# MCU.net
KiCad netlist of a schematic drawn in Altium Designer
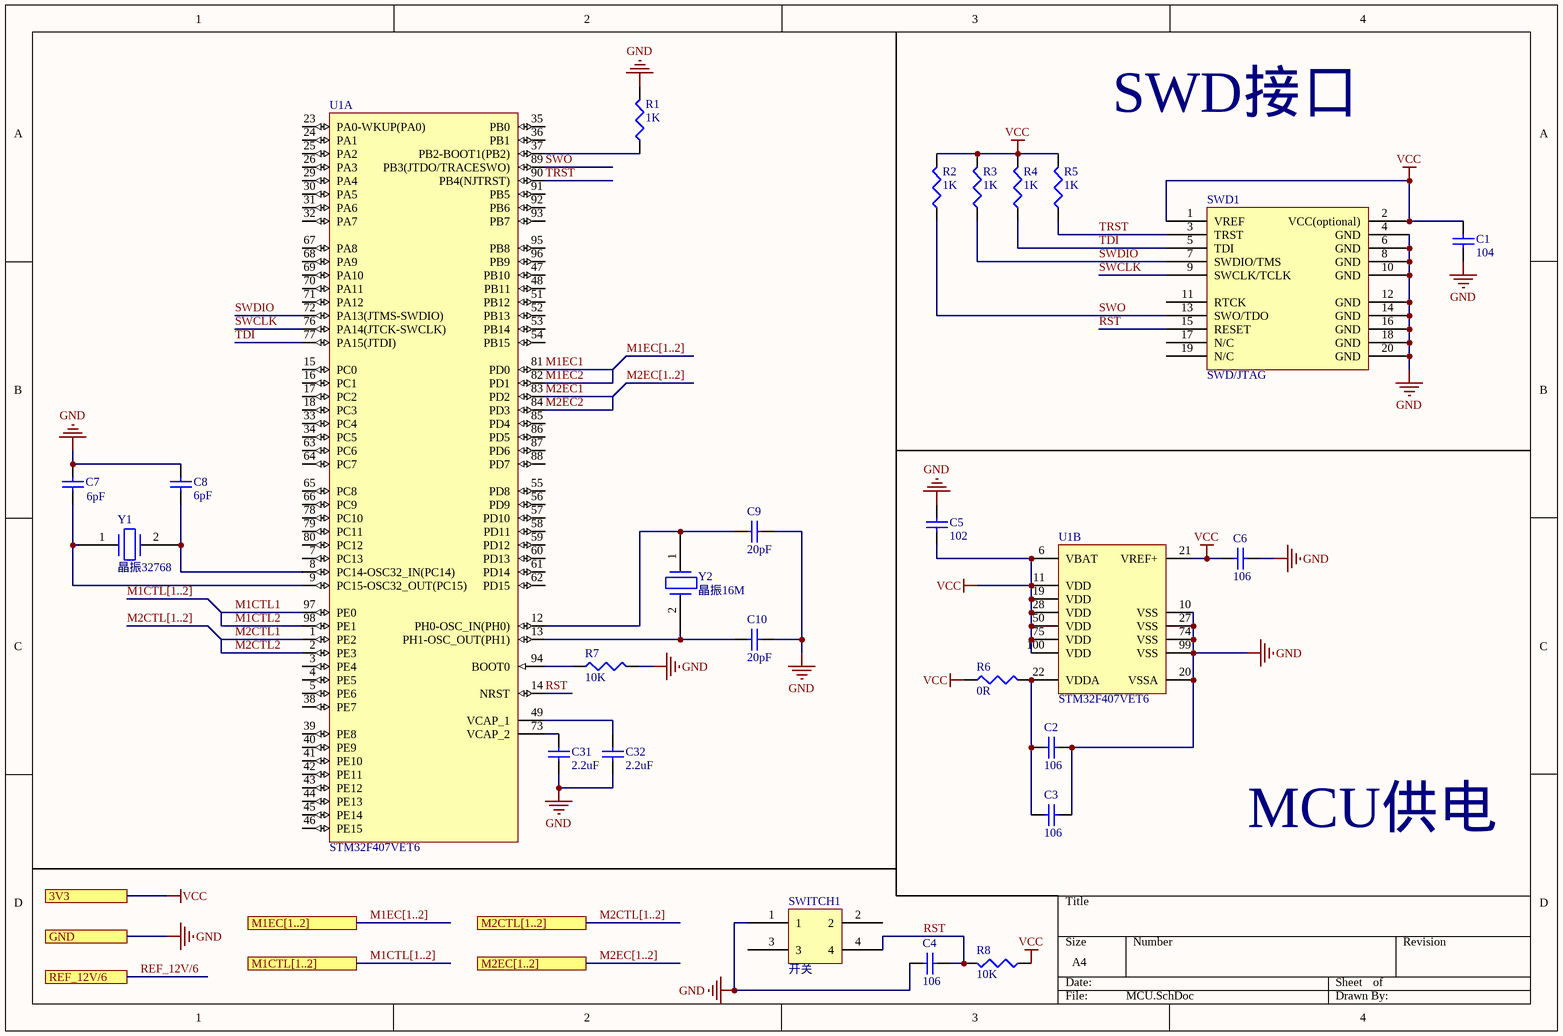
[diagram p0: MCU.SchDoc]

(export (version "E")
  (design (tool "Eeschema 10.0.6"))
  (components
    (comp (ref "C1")
      (value "104")
      (footprint "MY0805")
      (description "Capacitor")
      (fields (field (name "PUBLISHER") "Altium Limited"))
      (libsource (lib "Miscellaneous Devices") (part "Cap"))
    )
    (comp (ref "C2")
      (value "106")
      (footprint "MY0805")
      (description "Capacitor")
      (fields (field (name "PUBLISHER") "Altium Limited"))
      (libsource (lib "Miscellaneous Devices") (part "Cap"))
    )
    (comp (ref "C3")
      (value "106")
      (footprint "MY0805")
      (description "Capacitor")
      (fields (field (name "PUBLISHER") "Altium Limited"))
      (libsource (lib "Miscellaneous Devices") (part "Cap"))
    )
    (comp (ref "C4")
      (value "106")
      (footprint "MY0805")
      (description "Capacitor")
      (fields (field (name "PUBLISHER") "Altium Limited"))
      (libsource (lib "Miscellaneous Devices") (part "Cap"))
    )
    (comp (ref "C5")
      (value "102")
      (footprint "MY0805")
      (description "Capacitor")
      (fields (field (name "PUBLISHER") "Altium Limited"))
      (libsource (lib "Miscellaneous Devices") (part "Cap"))
    )
    (comp (ref "C6")
      (value "106")
      (footprint "MY0805")
      (description "Capacitor")
      (fields (field (name "PUBLISHER") "Altium Limited"))
      (libsource (lib "Miscellaneous Devices") (part "Cap"))
    )
    (comp (ref "C7")
      (value "6pF")
      (footprint "MY0805")
      (description "Capacitor")
      (fields (field (name "PUBLISHER") "Altium Limited"))
      (libsource (lib "Miscellaneous Devices") (part "Cap"))
    )
    (comp (ref "C8")
      (value "6pF")
      (footprint "MY0805")
      (description "Capacitor")
      (fields (field (name "PUBLISHER") "Altium Limited"))
      (libsource (lib "Miscellaneous Devices") (part "Cap"))
    )
    (comp (ref "C9")
      (value "20pF")
      (footprint "MY0805")
      (description "Capacitor")
      (fields (field (name "PUBLISHER") "Altium Limited"))
      (libsource (lib "Miscellaneous Devices") (part "Cap"))
    )
    (comp (ref "C10")
      (value "20pF")
      (footprint "MY0805")
      (description "Capacitor")
      (fields (field (name "PUBLISHER") "Altium Limited"))
      (libsource (lib "Miscellaneous Devices") (part "Cap"))
    )
    (comp (ref "C31")
      (value "2.2uF")
      (footprint "MY0805")
      (description "Capacitor")
      (fields (field (name "PUBLISHER") "Altium Limited"))
      (libsource (lib "Miscellaneous Devices") (part "Cap"))
    )
    (comp (ref "C32")
      (value "2.2uF")
      (footprint "MY0805")
      (description "Capacitor")
      (fields (field (name "PUBLISHER") "Altium Limited"))
      (libsource (lib "Miscellaneous Devices") (part "Cap"))
    )
    (comp (ref "R1")
      (value "1K")
      (footprint "MY0805")
      (description "Resistor")
      (fields (field (name "PUBLISHER") "Altium Limited"))
      (libsource (lib "Miscellaneous Devices") (part "Res3"))
    )
    (comp (ref "R2")
      (value "1K")
      (footprint "MY0805")
      (description "Resistor")
      (fields (field (name "PUBLISHER") "Altium Limited"))
      (libsource (lib "Miscellaneous Devices") (part "Res3"))
    )
    (comp (ref "R3")
      (value "1K")
      (footprint "MY0805")
      (description "Resistor")
      (fields (field (name "PUBLISHER") "Altium Limited"))
      (libsource (lib "Miscellaneous Devices") (part "Res3"))
    )
    (comp (ref "R4")
      (value "1K")
      (footprint "MY0805")
      (description "Resistor")
      (fields (field (name "PUBLISHER") "Altium Limited"))
      (libsource (lib "Miscellaneous Devices") (part "Res3"))
    )
    (comp (ref "R5")
      (value "1K")
      (footprint "MY0805")
      (description "Resistor")
      (fields (field (name "PUBLISHER") "Altium Limited"))
      (libsource (lib "Miscellaneous Devices") (part "Res3"))
    )
    (comp (ref "R6")
      (value "0R")
      (footprint "MY0805")
      (description "Resistor")
      (fields (field (name "PUBLISHER") "Altium Limited"))
      (libsource (lib "Miscellaneous Devices") (part "Res3"))
    )
    (comp (ref "R7")
      (value "10K")
      (footprint "MY0805")
      (description "Resistor")
      (fields (field (name "PUBLISHER") "Altium Limited"))
      (libsource (lib "Miscellaneous Devices") (part "Res3"))
    )
    (comp (ref "R8")
      (value "10K")
      (footprint "MY0805")
      (description "Resistor")
      (fields (field (name "PUBLISHER") "Altium Limited"))
      (libsource (lib "Miscellaneous Devices") (part "Res3"))
    )
    (comp (ref "SWD1") (value "SWD/JTAG") (footprint "SWD") (libsource (lib "Schlib1") (part "SWD/JTAG")))
    (comp (ref "SWITCH1") (value "开关") (footprint "开关") (libsource (lib "Schlib1") (part "开关")))
    (comp (ref "U1")
      (value "STM32F407VET6")
      (footprint "STM-LQFP100_N")
      (fields (field (name "MANUFACTURER") "STMicroelectronics"))
      (libsource (lib "STMicroelectronics STM32 F4") (part "STM32F407VET6"))
    )
    (comp (ref "Y1") (value "晶振32768") (footprint "晶振32768K_AT38") (libsource (lib "Schlib1") (part "晶振")))
    (comp (ref "Y2") (value "晶振16M") (footprint "晶振16M") (libsource (lib "Schlib1") (part "晶振")))
  )
  (nets
    (net (code "1") (name "/M1CTL1") (class "Default")
      (node (ref "U1") (pin "97") (pinfunction "PE0_97") (pintype "bidirectional"))
    )
    (net (code "2") (name "/M1CTL2") (class "Default")
      (node (ref "U1") (pin "98") (pinfunction "PE1_98") (pintype "bidirectional"))
    )
    (net (code "4") (name "/M1EC1") (class "Default")
      (node (ref "U1") (pin "81") (pinfunction "PD0_81") (pintype "bidirectional"))
    )
    (net (code "5") (name "/M1EC2") (class "Default")
      (node (ref "U1") (pin "82") (pinfunction "PD1_82") (pintype "bidirectional"))
    )
    (net (code "7") (name "/M2CTL1") (class "Default")
      (node (ref "U1") (pin "1") (pinfunction "PE2_1") (pintype "bidirectional"))
    )
    (net (code "8") (name "/M2CTL2") (class "Default")
      (node (ref "U1") (pin "2") (pinfunction "PE3_2") (pintype "bidirectional"))
    )
    (net (code "10") (name "/M2EC1") (class "Default")
      (node (ref "U1") (pin "83") (pinfunction "PD2_83") (pintype "bidirectional"))
    )
    (net (code "11") (name "/M2EC2") (class "Default")
      (node (ref "U1") (pin "84") (pinfunction "PD3_84") (pintype "bidirectional"))
    )
    (net (code "14") (name "/RST") (class "Default")
      (node (ref "C4") (pin "2") (pinfunction "2_2") (pintype "passive"))
      (node (ref "R8") (pin "2") (pinfunction "2_2") (pintype "passive"))
      (node (ref "SWD1") (pin "15") (pinfunction "RESET_15") (pintype "passive"))
      (node (ref "SWITCH1") (pin "4") (pinfunction "4_4") (pintype "passive"))
      (node (ref "U1") (pin "14") (pinfunction "NRST_14") (pintype "bidirectional"))
    )
    (net (code "15") (name "/SWCLK") (class "Default")
      (node (ref "SWD1") (pin "9") (pinfunction "SWCLK/TCLK_9") (pintype "passive"))
      (node (ref "U1") (pin "76") (pinfunction "PA14(JTCK-SWCLK)_76") (pintype "bidirectional"))
    )
    (net (code "16") (name "/SWDIO") (class "Default")
      (node (ref "R3") (pin "1") (pinfunction "1_1") (pintype "passive"))
      (node (ref "SWD1") (pin "7") (pinfunction "SWDIO/TMS_7") (pintype "passive"))
      (node (ref "U1") (pin "72") (pinfunction "PA13(JTMS-SWDIO)_72") (pintype "bidirectional"))
    )
    (net (code "17") (name "/SWO") (class "Default")
      (node (ref "R2") (pin "1") (pinfunction "1_1") (pintype "passive"))
      (node (ref "SWD1") (pin "13") (pinfunction "SWO/TDO_13") (pintype "passive"))
      (node (ref "U1") (pin "89") (pinfunction "PB3(JTDO/TRACESWO)_89") (pintype "bidirectional"))
    )
    (net (code "18") (name "/TDI") (class "Default")
      (node (ref "R4") (pin "1") (pinfunction "1_1") (pintype "passive"))
      (node (ref "SWD1") (pin "5") (pinfunction "TDI_5") (pintype "passive"))
      (node (ref "U1") (pin "77") (pinfunction "PA15(JTDI)_77") (pintype "bidirectional"))
    )
    (net (code "19") (name "/TRST") (class "Default")
      (node (ref "R5") (pin "1") (pinfunction "1_1") (pintype "passive"))
      (node (ref "SWD1") (pin "3") (pinfunction "TRST_3") (pintype "passive"))
      (node (ref "U1") (pin "90") (pinfunction "PB4(NJTRST)_90") (pintype "bidirectional"))
    )
    (net (code "20") (name "GND") (class "Default")
      (node (ref "C1") (pin "1") (pinfunction "1_1") (pintype "passive"))
      (node (ref "C10") (pin "2") (pinfunction "2_2") (pintype "passive"))
      (node (ref "C2") (pin "2") (pinfunction "2_2") (pintype "passive"))
      (node (ref "C3") (pin "2") (pinfunction "2_2") (pintype "passive"))
      (node (ref "C31") (pin "1") (pinfunction "1_1") (pintype "passive"))
      (node (ref "C32") (pin "1") (pinfunction "1_1") (pintype "passive"))
      (node (ref "C4") (pin "1") (pinfunction "1_1") (pintype "passive"))
      (node (ref "C5") (pin "1") (pinfunction "1_1") (pintype "passive"))
      (node (ref "C6") (pin "2") (pinfunction "2_2") (pintype "passive"))
      (node (ref "C7") (pin "2") (pinfunction "2_2") (pintype "passive"))
      (node (ref "C8") (pin "2") (pinfunction "2_2") (pintype "passive"))
      (node (ref "C9") (pin "2") (pinfunction "2_2") (pintype "passive"))
      (node (ref "R1") (pin "2") (pinfunction "2_2") (pintype "passive"))
      (node (ref "R7") (pin "2") (pinfunction "2_2") (pintype "passive"))
      (node (ref "SWD1") (pin "10") (pinfunction "GND_10") (pintype "passive"))
      (node (ref "SWD1") (pin "12") (pinfunction "GND_12") (pintype "passive"))
      (node (ref "SWD1") (pin "14") (pinfunction "GND_14") (pintype "passive"))
      (node (ref "SWD1") (pin "16") (pinfunction "GND_16") (pintype "passive"))
      (node (ref "SWD1") (pin "18") (pinfunction "GND_18") (pintype "passive"))
      (node (ref "SWD1") (pin "20") (pinfunction "GND_20") (pintype "passive"))
      (node (ref "SWD1") (pin "4") (pinfunction "GND_4") (pintype "passive"))
      (node (ref "SWD1") (pin "6") (pinfunction "GND_6") (pintype "passive"))
      (node (ref "SWD1") (pin "8") (pinfunction "GND_8") (pintype "passive"))
      (node (ref "SWITCH1") (pin "1") (pinfunction "1_1") (pintype "passive"))
      (node (ref "U1") (pin "10") (pinfunction "VSS_10") (pintype "power_in"))
      (node (ref "U1") (pin "20") (pinfunction "VSSA_20") (pintype "power_in"))
      (node (ref "U1") (pin "27") (pinfunction "VSS_27") (pintype "power_in"))
      (node (ref "U1") (pin "74") (pinfunction "VSS_74") (pintype "power_in"))
      (node (ref "U1") (pin "99") (pinfunction "VSS_99") (pintype "power_in"))
    )
    (net (code "21") (name "Net-(U1A-BOOT0)") (class "Default")
      (node (ref "R7") (pin "1") (pinfunction "1_1") (pintype "passive"))
      (node (ref "U1") (pin "94") (pinfunction "BOOT0_94") (pintype "input"))
    )
    (net (code "22") (name "Net-(U1A-PB2-BOOT1(PB2))") (class "Default")
      (node (ref "R1") (pin "1") (pinfunction "1_1") (pintype "passive"))
      (node (ref "U1") (pin "37") (pinfunction "PB2-BOOT1(PB2)_37") (pintype "bidirectional"))
    )
    (net (code "23") (name "Net-(U1A-PC14-OSC32_IN(PC14))") (class "Default")
      (node (ref "C8") (pin "1") (pinfunction "1_1") (pintype "passive"))
      (node (ref "U1") (pin "8") (pinfunction "PC14-OSC32_IN(PC14)_8") (pintype "bidirectional"))
      (node (ref "Y1") (pin "2") (pinfunction "2_2") (pintype "passive"))
    )
    (net (code "24") (name "Net-(U1A-PC15-OSC32_OUT(PC15))") (class "Default")
      (node (ref "C7") (pin "1") (pinfunction "1_1") (pintype "passive"))
      (node (ref "U1") (pin "9") (pinfunction "PC15-OSC32_OUT(PC15)_9") (pintype "bidirectional"))
      (node (ref "Y1") (pin "1") (pinfunction "1_1") (pintype "passive"))
    )
    (net (code "25") (name "Net-(U1A-PH0-OSC_IN(PH0))") (class "Default")
      (node (ref "C9") (pin "1") (pinfunction "1_1") (pintype "passive"))
      (node (ref "U1") (pin "12") (pinfunction "PH0-OSC_IN(PH0)_12") (pintype "bidirectional"))
      (node (ref "Y2") (pin "1") (pinfunction "1_1") (pintype "passive"))
    )
    (net (code "26") (name "Net-(U1A-PH1-OSC_OUT(PH1))") (class "Default")
      (node (ref "C10") (pin "1") (pinfunction "1_1") (pintype "passive"))
      (node (ref "U1") (pin "13") (pinfunction "PH1-OSC_OUT(PH1)_13") (pintype "bidirectional"))
      (node (ref "Y2") (pin "2") (pinfunction "2_2") (pintype "passive"))
    )
    (net (code "27") (name "Net-(U1A-VCAP_1)") (class "Default")
      (node (ref "C32") (pin "2") (pinfunction "2_2") (pintype "passive"))
      (node (ref "U1") (pin "49") (pinfunction "VCAP_1_49") (pintype "power_in"))
    )
    (net (code "28") (name "Net-(U1A-VCAP_2)") (class "Default")
      (node (ref "C31") (pin "2") (pinfunction "2_2") (pintype "passive"))
      (node (ref "U1") (pin "73") (pinfunction "VCAP_2_73") (pintype "power_in"))
    )
    (net (code "29") (name "Net-(U1B-VDDA)") (class "Default")
      (node (ref "C2") (pin "1") (pinfunction "1_1") (pintype "passive"))
      (node (ref "C3") (pin "1") (pinfunction "1_1") (pintype "passive"))
      (node (ref "R6") (pin "2") (pinfunction "2_2") (pintype "passive"))
      (node (ref "U1") (pin "22") (pinfunction "VDDA_22") (pintype "power_in"))
    )
    (net (code "30") (name "VCC") (class "Default")
      (node (ref "C1") (pin "2") (pinfunction "2_2") (pintype "passive"))
      (node (ref "C5") (pin "2") (pinfunction "2_2") (pintype "passive"))
      (node (ref "C6") (pin "1") (pinfunction "1_1") (pintype "passive"))
      (node (ref "R2") (pin "2") (pinfunction "2_2") (pintype "passive"))
      (node (ref "R3") (pin "2") (pinfunction "2_2") (pintype "passive"))
      (node (ref "R4") (pin "2") (pinfunction "2_2") (pintype "passive"))
      (node (ref "R5") (pin "2") (pinfunction "2_2") (pintype "passive"))
      (node (ref "R6") (pin "1") (pinfunction "1_1") (pintype "passive"))
      (node (ref "R8") (pin "1") (pinfunction "1_1") (pintype "passive"))
      (node (ref "SWD1") (pin "1") (pinfunction "VREF_1") (pintype "passive"))
      (node (ref "SWD1") (pin "2") (pinfunction "VCC(optional)_2") (pintype "passive"))
      (node (ref "U1") (pin "100") (pinfunction "VDD_100") (pintype "power_in"))
      (node (ref "U1") (pin "11") (pinfunction "VDD_11") (pintype "power_in"))
      (node (ref "U1") (pin "19") (pinfunction "VDD_19") (pintype "power_in"))
      (node (ref "U1") (pin "21") (pinfunction "VREF+_21") (pintype "power_in"))
      (node (ref "U1") (pin "28") (pinfunction "VDD_28") (pintype "power_in"))
      (node (ref "U1") (pin "50") (pinfunction "VDD_50") (pintype "power_in"))
      (node (ref "U1") (pin "6") (pinfunction "VBAT_6") (pintype "power_in"))
      (node (ref "U1") (pin "75") (pinfunction "VDD_75") (pintype "power_in"))
    )
    (net (code "31") (name "unconnected-(SWD1-N{slash}C-Pad17)") (class "Default")
      (node (ref "SWD1") (pin "17") (pinfunction "N/C_17") (pintype "passive"))
    )
    (net (code "32") (name "unconnected-(SWD1-N{slash}C-Pad19)") (class "Default")
      (node (ref "SWD1") (pin "19") (pinfunction "N/C_19") (pintype "passive"))
    )
    (net (code "33") (name "unconnected-(SWD1-RTCK-Pad11)") (class "Default")
      (node (ref "SWD1") (pin "11") (pinfunction "RTCK_11") (pintype "passive"))
    )
    (net (code "34") (name "unconnected-(SWITCH1-Pad2)") (class "Default")
      (node (ref "SWITCH1") (pin "2") (pinfunction "2_2") (pintype "passive"))
    )
    (net (code "35") (name "unconnected-(SWITCH1-Pad3)") (class "Default")
      (node (ref "SWITCH1") (pin "3") (pinfunction "3_3") (pintype "passive"))
    )
    (net (code "36") (name "unconnected-(U1A-PA0-WKUP(PA0)-Pad23)") (class "Default")
      (node (ref "U1") (pin "23") (pinfunction "PA0-WKUP(PA0)_23") (pintype "bidirectional"))
    )
    (net (code "37") (name "unconnected-(U1A-PA1-Pad24)") (class "Default")
      (node (ref "U1") (pin "24") (pinfunction "PA1_24") (pintype "bidirectional"))
    )
    (net (code "38") (name "unconnected-(U1A-PA2-Pad25)") (class "Default")
      (node (ref "U1") (pin "25") (pinfunction "PA2_25") (pintype "bidirectional"))
    )
    (net (code "39") (name "unconnected-(U1A-PA3-Pad26)") (class "Default")
      (node (ref "U1") (pin "26") (pinfunction "PA3_26") (pintype "bidirectional"))
    )
    (net (code "40") (name "unconnected-(U1A-PA4-Pad29)") (class "Default")
      (node (ref "U1") (pin "29") (pinfunction "PA4_29") (pintype "bidirectional"))
    )
    (net (code "41") (name "unconnected-(U1A-PA5-Pad30)") (class "Default")
      (node (ref "U1") (pin "30") (pinfunction "PA5_30") (pintype "bidirectional"))
    )
    (net (code "42") (name "unconnected-(U1A-PA6-Pad31)") (class "Default")
      (node (ref "U1") (pin "31") (pinfunction "PA6_31") (pintype "bidirectional"))
    )
    (net (code "43") (name "unconnected-(U1A-PA7-Pad32)") (class "Default")
      (node (ref "U1") (pin "32") (pinfunction "PA7_32") (pintype "bidirectional"))
    )
    (net (code "44") (name "unconnected-(U1A-PA8-Pad67)") (class "Default")
      (node (ref "U1") (pin "67") (pinfunction "PA8_67") (pintype "bidirectional"))
    )
    (net (code "45") (name "unconnected-(U1A-PA9-Pad68)") (class "Default")
      (node (ref "U1") (pin "68") (pinfunction "PA9_68") (pintype "bidirectional"))
    )
    (net (code "46") (name "unconnected-(U1A-PA10-Pad69)") (class "Default")
      (node (ref "U1") (pin "69") (pinfunction "PA10_69") (pintype "bidirectional"))
    )
    (net (code "47") (name "unconnected-(U1A-PA11-Pad70)") (class "Default")
      (node (ref "U1") (pin "70") (pinfunction "PA11_70") (pintype "bidirectional"))
    )
    (net (code "48") (name "unconnected-(U1A-PA12-Pad71)") (class "Default")
      (node (ref "U1") (pin "71") (pinfunction "PA12_71") (pintype "bidirectional"))
    )
    (net (code "49") (name "unconnected-(U1A-PB0-Pad35)") (class "Default")
      (node (ref "U1") (pin "35") (pinfunction "PB0_35") (pintype "bidirectional"))
    )
    (net (code "50") (name "unconnected-(U1A-PB1-Pad36)") (class "Default")
      (node (ref "U1") (pin "36") (pinfunction "PB1_36") (pintype "bidirectional"))
    )
    (net (code "51") (name "unconnected-(U1A-PB5-Pad91)") (class "Default")
      (node (ref "U1") (pin "91") (pinfunction "PB5_91") (pintype "bidirectional"))
    )
    (net (code "52") (name "unconnected-(U1A-PB6-Pad92)") (class "Default")
      (node (ref "U1") (pin "92") (pinfunction "PB6_92") (pintype "bidirectional"))
    )
    (net (code "53") (name "unconnected-(U1A-PB7-Pad93)") (class "Default")
      (node (ref "U1") (pin "93") (pinfunction "PB7_93") (pintype "bidirectional"))
    )
    (net (code "54") (name "unconnected-(U1A-PB8-Pad95)") (class "Default")
      (node (ref "U1") (pin "95") (pinfunction "PB8_95") (pintype "bidirectional"))
    )
    (net (code "55") (name "unconnected-(U1A-PB9-Pad96)") (class "Default")
      (node (ref "U1") (pin "96") (pinfunction "PB9_96") (pintype "bidirectional"))
    )
    (net (code "56") (name "unconnected-(U1A-PB10-Pad47)") (class "Default")
      (node (ref "U1") (pin "47") (pinfunction "PB10_47") (pintype "bidirectional"))
    )
    (net (code "57") (name "unconnected-(U1A-PB11-Pad48)") (class "Default")
      (node (ref "U1") (pin "48") (pinfunction "PB11_48") (pintype "bidirectional"))
    )
    (net (code "58") (name "unconnected-(U1A-PB12-Pad51)") (class "Default")
      (node (ref "U1") (pin "51") (pinfunction "PB12_51") (pintype "bidirectional"))
    )
    (net (code "59") (name "unconnected-(U1A-PB13-Pad52)") (class "Default")
      (node (ref "U1") (pin "52") (pinfunction "PB13_52") (pintype "bidirectional"))
    )
    (net (code "60") (name "unconnected-(U1A-PB14-Pad53)") (class "Default")
      (node (ref "U1") (pin "53") (pinfunction "PB14_53") (pintype "bidirectional"))
    )
    (net (code "61") (name "unconnected-(U1A-PB15-Pad54)") (class "Default")
      (node (ref "U1") (pin "54") (pinfunction "PB15_54") (pintype "bidirectional"))
    )
    (net (code "62") (name "unconnected-(U1A-PC0-Pad15)") (class "Default")
      (node (ref "U1") (pin "15") (pinfunction "PC0_15") (pintype "bidirectional"))
    )
    (net (code "63") (name "unconnected-(U1A-PC1-Pad16)") (class "Default")
      (node (ref "U1") (pin "16") (pinfunction "PC1_16") (pintype "bidirectional"))
    )
    (net (code "64") (name "unconnected-(U1A-PC2-Pad17)") (class "Default")
      (node (ref "U1") (pin "17") (pinfunction "PC2_17") (pintype "bidirectional"))
    )
    (net (code "65") (name "unconnected-(U1A-PC3-Pad18)") (class "Default")
      (node (ref "U1") (pin "18") (pinfunction "PC3_18") (pintype "bidirectional"))
    )
    (net (code "66") (name "unconnected-(U1A-PC4-Pad33)") (class "Default")
      (node (ref "U1") (pin "33") (pinfunction "PC4_33") (pintype "bidirectional"))
    )
    (net (code "67") (name "unconnected-(U1A-PC5-Pad34)") (class "Default")
      (node (ref "U1") (pin "34") (pinfunction "PC5_34") (pintype "bidirectional"))
    )
    (net (code "68") (name "unconnected-(U1A-PC6-Pad63)") (class "Default")
      (node (ref "U1") (pin "63") (pinfunction "PC6_63") (pintype "bidirectional"))
    )
    (net (code "69") (name "unconnected-(U1A-PC7-Pad64)") (class "Default")
      (node (ref "U1") (pin "64") (pinfunction "PC7_64") (pintype "bidirectional"))
    )
    (net (code "70") (name "unconnected-(U1A-PC8-Pad65)") (class "Default")
      (node (ref "U1") (pin "65") (pinfunction "PC8_65") (pintype "bidirectional"))
    )
    (net (code "71") (name "unconnected-(U1A-PC9-Pad66)") (class "Default")
      (node (ref "U1") (pin "66") (pinfunction "PC9_66") (pintype "bidirectional"))
    )
    (net (code "72") (name "unconnected-(U1A-PC10-Pad78)") (class "Default")
      (node (ref "U1") (pin "78") (pinfunction "PC10_78") (pintype "bidirectional"))
    )
    (net (code "73") (name "unconnected-(U1A-PC11-Pad79)") (class "Default")
      (node (ref "U1") (pin "79") (pinfunction "PC11_79") (pintype "bidirectional"))
    )
    (net (code "74") (name "unconnected-(U1A-PC12-Pad80)") (class "Default")
      (node (ref "U1") (pin "80") (pinfunction "PC12_80") (pintype "bidirectional"))
    )
    (net (code "75") (name "unconnected-(U1A-PC13-Pad7)") (class "Default")
      (node (ref "U1") (pin "7") (pinfunction "PC13_7") (pintype "bidirectional"))
    )
    (net (code "76") (name "unconnected-(U1A-PD4-Pad85)") (class "Default")
      (node (ref "U1") (pin "85") (pinfunction "PD4_85") (pintype "bidirectional"))
    )
    (net (code "77") (name "unconnected-(U1A-PD5-Pad86)") (class "Default")
      (node (ref "U1") (pin "86") (pinfunction "PD5_86") (pintype "bidirectional"))
    )
    (net (code "78") (name "unconnected-(U1A-PD6-Pad87)") (class "Default")
      (node (ref "U1") (pin "87") (pinfunction "PD6_87") (pintype "bidirectional"))
    )
    (net (code "79") (name "unconnected-(U1A-PD7-Pad88)") (class "Default")
      (node (ref "U1") (pin "88") (pinfunction "PD7_88") (pintype "bidirectional"))
    )
    (net (code "80") (name "unconnected-(U1A-PD8-Pad55)") (class "Default")
      (node (ref "U1") (pin "55") (pinfunction "PD8_55") (pintype "bidirectional"))
    )
    (net (code "81") (name "unconnected-(U1A-PD9-Pad56)") (class "Default")
      (node (ref "U1") (pin "56") (pinfunction "PD9_56") (pintype "bidirectional"))
    )
    (net (code "82") (name "unconnected-(U1A-PD10-Pad57)") (class "Default")
      (node (ref "U1") (pin "57") (pinfunction "PD10_57") (pintype "bidirectional"))
    )
    (net (code "83") (name "unconnected-(U1A-PD11-Pad58)") (class "Default")
      (node (ref "U1") (pin "58") (pinfunction "PD11_58") (pintype "bidirectional"))
    )
    (net (code "84") (name "unconnected-(U1A-PD12-Pad59)") (class "Default")
      (node (ref "U1") (pin "59") (pinfunction "PD12_59") (pintype "bidirectional"))
    )
    (net (code "85") (name "unconnected-(U1A-PD13-Pad60)") (class "Default")
      (node (ref "U1") (pin "60") (pinfunction "PD13_60") (pintype "bidirectional"))
    )
    (net (code "86") (name "unconnected-(U1A-PD14-Pad61)") (class "Default")
      (node (ref "U1") (pin "61") (pinfunction "PD14_61") (pintype "bidirectional"))
    )
    (net (code "87") (name "unconnected-(U1A-PD15-Pad62)") (class "Default")
      (node (ref "U1") (pin "62") (pinfunction "PD15_62") (pintype "bidirectional"))
    )
    (net (code "88") (name "unconnected-(U1A-PE4-Pad3)") (class "Default")
      (node (ref "U1") (pin "3") (pinfunction "PE4_3") (pintype "bidirectional"))
    )
    (net (code "89") (name "unconnected-(U1A-PE5-Pad4)") (class "Default")
      (node (ref "U1") (pin "4") (pinfunction "PE5_4") (pintype "bidirectional"))
    )
    (net (code "90") (name "unconnected-(U1A-PE6-Pad5)") (class "Default")
      (node (ref "U1") (pin "5") (pinfunction "PE6_5") (pintype "bidirectional"))
    )
    (net (code "91") (name "unconnected-(U1A-PE7-Pad38)") (class "Default")
      (node (ref "U1") (pin "38") (pinfunction "PE7_38") (pintype "bidirectional"))
    )
    (net (code "92") (name "unconnected-(U1A-PE8-Pad39)") (class "Default")
      (node (ref "U1") (pin "39") (pinfunction "PE8_39") (pintype "bidirectional"))
    )
    (net (code "93") (name "unconnected-(U1A-PE9-Pad40)") (class "Default")
      (node (ref "U1") (pin "40") (pinfunction "PE9_40") (pintype "bidirectional"))
    )
    (net (code "94") (name "unconnected-(U1A-PE10-Pad41)") (class "Default")
      (node (ref "U1") (pin "41") (pinfunction "PE10_41") (pintype "bidirectional"))
    )
    (net (code "95") (name "unconnected-(U1A-PE11-Pad42)") (class "Default")
      (node (ref "U1") (pin "42") (pinfunction "PE11_42") (pintype "bidirectional"))
    )
    (net (code "96") (name "unconnected-(U1A-PE12-Pad43)") (class "Default")
      (node (ref "U1") (pin "43") (pinfunction "PE12_43") (pintype "bidirectional"))
    )
    (net (code "97") (name "unconnected-(U1A-PE13-Pad44)") (class "Default")
      (node (ref "U1") (pin "44") (pinfunction "PE13_44") (pintype "bidirectional"))
    )
    (net (code "98") (name "unconnected-(U1A-PE14-Pad45)") (class "Default")
      (node (ref "U1") (pin "45") (pinfunction "PE14_45") (pintype "bidirectional"))
    )
    (net (code "99") (name "unconnected-(U1A-PE15-Pad46)") (class "Default")
      (node (ref "U1") (pin "46") (pinfunction "PE15_46") (pintype "bidirectional"))
    )
  )
)
